# Sheet1.net
KiCad netlist of a schematic drawn in Altium Designer
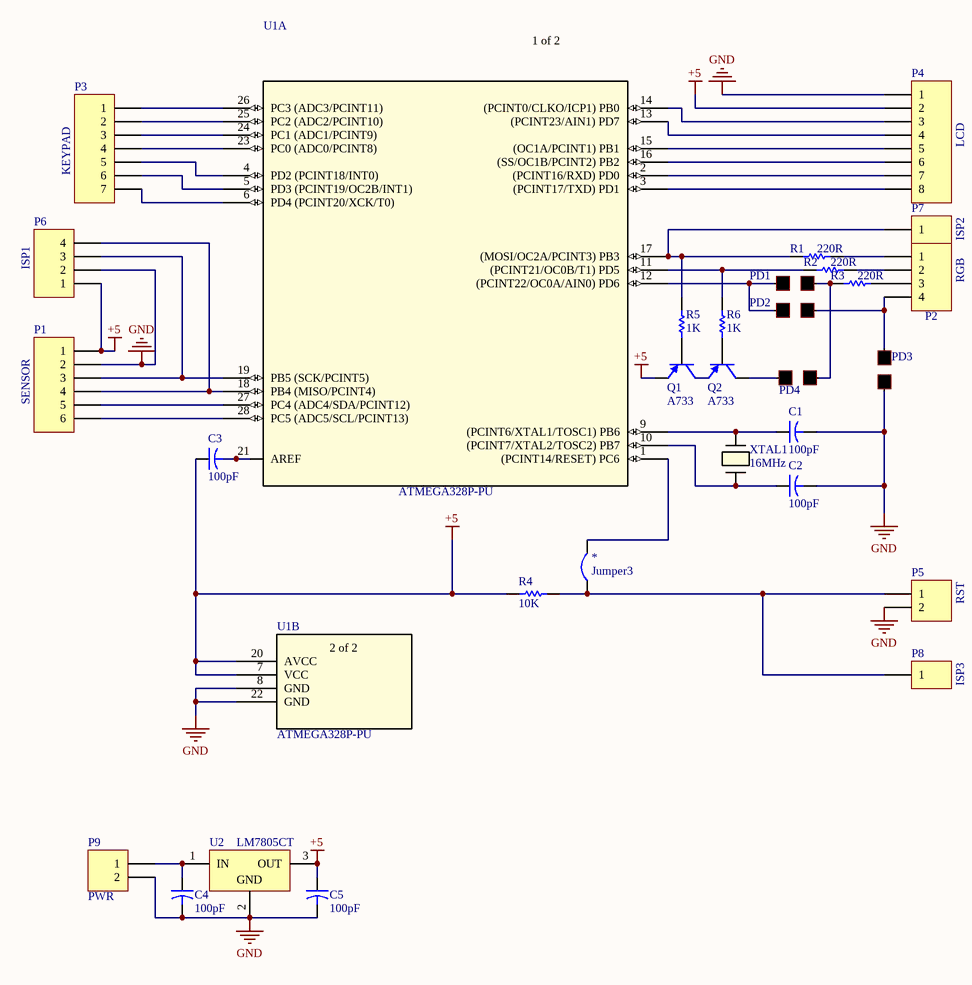
[diagram p0: Sheet1.SchDoc]

(export (version "E")
  (design (tool "Eeschema 10.0.6"))
  (components
    (comp (ref "*") (value "Jumper3") (footprint "JUMPER3") (libsource (lib "Common Parts") (part "Jumper3")))
    (comp (ref "C1")
      (value "100pF")
      (footprint "CAP1")
      (description "Capacitor")
      (fields (field (name "PUBLISHER") "Altium Limited"))
      (libsource (lib "Common Parts") (part "Cap1"))
    )
    (comp (ref "C2")
      (value "100pF")
      (footprint "CAP1")
      (description "Capacitor")
      (fields (field (name "PUBLISHER") "Altium Limited"))
      (libsource (lib "Common Parts") (part "Cap1"))
    )
    (comp (ref "C3")
      (value "100pF")
      (footprint "CAP1")
      (description "Capacitor")
      (fields (field (name "PUBLISHER") "Altium Limited"))
      (libsource (lib "Common Parts") (part "Cap1"))
    )
    (comp (ref "C4")
      (value "100pF")
      (footprint "CAP1")
      (description "Capacitor")
      (fields (field (name "PUBLISHER") "Altium Limited"))
      (libsource (lib "Common Parts") (part "Cap1"))
    )
    (comp (ref "C5")
      (value "100pF")
      (footprint "CAP1")
      (description "Capacitor")
      (fields (field (name "PUBLISHER") "Altium Limited"))
      (libsource (lib "Common Parts") (part "Cap1"))
    )
    (comp (ref "P1")
      (value "SENSOR")
      (footprint "H6")
      (description "Header, 6-Pin")
      (fields (field (name "PUBLISHER") "Altium Limited"))
      (libsource (lib "Miscellaneous Connectors") (part "Header 6"))
    )
    (comp (ref "P2")
      (value "RGB")
      (footprint "H4")
      (description "Header, 4-Pin")
      (fields (field (name "PUBLISHER") "Altium Limited"))
      (libsource (lib "") (part "Header 4_1"))
    )
    (comp (ref "P3")
      (value "KEYPAD")
      (footprint "H7")
      (description "Header, 7-Pin")
      (fields (field (name "PUBLISHER") "Altium Limited"))
      (libsource (lib "Miscellaneous Connectors") (part "Header 7"))
    )
    (comp (ref "P4")
      (value "LCD")
      (footprint "H8")
      (description "Header, 8-Pin")
      (fields (field (name "PUBLISHER") "Altium Limited"))
      (libsource (lib "Miscellaneous Connectors") (part "Header 8"))
    )
    (comp (ref "P5")
      (value "RST")
      (footprint "H2")
      (description "Header, 2-Pin")
      (fields (field (name "PUBLISHER") "Altium Limited"))
      (libsource (lib "Miscellaneous Connectors") (part "Header 2"))
    )
    (comp (ref "P6")
      (value "ISP1")
      (footprint "H4")
      (description "Header, 4-Pin")
      (fields (field (name "PUBLISHER") "Altium Limited"))
      (libsource (lib "Miscellaneous Connectors") (part "Header 4"))
    )
    (comp (ref "P7")
      (value "ISP2")
      (footprint "H1")
      (description "Header, 1-Pin")
      (fields (field (name "PUBLISHER") "Altium Limited"))
      (libsource (lib "Footprints_lib") (part "Header 1"))
    )
    (comp (ref "P8")
      (value "ISP3")
      (footprint "H1")
      (description "Header, 1-Pin")
      (fields (field (name "PUBLISHER") "Altium Limited"))
      (libsource (lib "Footprints_lib") (part "Header 1"))
    )
    (comp (ref "P9")
      (value "PWR")
      (footprint "H2_PWR")
      (description "Header, 2-Pin")
      (fields (field (name "PUBLISHER") "Altium Limited"))
      (libsource (lib "Footprints_lib") (part "Header 2"))
    )
    (comp (ref "PD1")
      (value "Pad2")
      (footprint "PAD2")
      (description "Square Pad")
      (libsource (lib "") (part "Pad2_1"))
    )
    (comp (ref "PD2")
      (value "Pad2")
      (footprint "PAD2")
      (description "Square Pad")
      (libsource (lib "") (part "Pad2_1"))
    )
    (comp (ref "PD3")
      (value "Pad2")
      (footprint "PAD2")
      (description "Square Pad")
      (libsource (lib "Common Parts") (part "Pad2"))
    )
    (comp (ref "PD4")
      (value "Pad2")
      (footprint "PAD2")
      (description "Square Pad")
      (libsource (lib "") (part "Pad2_2"))
    )
    (comp (ref "Q1")
      (value "A733")
      (footprint "TO-92_ONS")
      (description "PNP General Purpose Transistor")
      (fields (field (name "PUBLISHER") "Altium Limited"))
      (libsource (lib "Common Parts") (part "A733"))
    )
    (comp (ref "Q2")
      (value "A733")
      (footprint "TO-92_ONS")
      (description "PNP General Purpose Transistor")
      (fields (field (name "PUBLISHER") "Altium Limited"))
      (libsource (lib "Common Parts") (part "A733"))
    )
    (comp (ref "R1")
      (value "220R")
      (footprint "RES")
      (description "Resistor")
      (fields (field (name "PUBLISHER") "Altium Limited"))
      (libsource (lib "Miscellaneous Devices") (part "Res1"))
    )
    (comp (ref "R2")
      (value "220R")
      (footprint "RES")
      (description "Resistor")
      (fields (field (name "PUBLISHER") "Altium Limited"))
      (libsource (lib "Miscellaneous Devices") (part "Res1"))
    )
    (comp (ref "R3")
      (value "220R")
      (footprint "RES")
      (description "Resistor")
      (fields (field (name "PUBLISHER") "Altium Limited"))
      (libsource (lib "Miscellaneous Devices") (part "Res1"))
    )
    (comp (ref "R4")
      (value "10K")
      (footprint "RES")
      (description "Resistor")
      (fields (field (name "PUBLISHER") "Altium Limited"))
      (libsource (lib "Common Parts") (part "Res1"))
    )
    (comp (ref "R5")
      (value "1K")
      (footprint "RES")
      (description "Resistor")
      (fields (field (name "PUBLISHER") "Altium Limited"))
      (libsource (lib "Miscellaneous Devices") (part "Res1"))
    )
    (comp (ref "R6")
      (value "1K")
      (footprint "RES")
      (description "Resistor")
      (fields (field (name "PUBLISHER") "Altium Limited"))
      (libsource (lib "Miscellaneous Devices") (part "Res1"))
    )
    (comp (ref "U1")
      (value "ATMEGA328P-PU")
      (footprint "28P3_ATM")
      (description "No Description Available")
      (fields (field (name "COPYRIGHT") "Copyright (C) 2018 Accelerated Designs. All rights reserved"))
      (libsource (lib "") (part "ATMEGA328P-PU_1"))
    )
    (comp (ref "U2")
      (value "LM7805CT")
      (footprint "FAIR-TO-220-3")
      (description "Positive Voltage Regulator, 5 V, 1 A, -40 to 125 degC, 3-Pin TO-220, RoHS, Tube")
      (fields (field (name "MANUFACTURER") "FairchildSemiconductor"))
      (libsource (lib "Altium Content Vault") (part "FAIR-LM7805CT-TO220-3"))
    )
    (comp (ref "XTAL1")
      (value "16MHz")
      (footprint "XTAL_9B_TXC")
      (description "No Description Available")
      (fields
        (field (name "MANUFACTURER_PART_NUMBER") "9B-11.0592MAAJ-B")
        (field (name "COPYRIGHT") "Copyright (C) 2018 Accelerated Designs. All rights reserved")
      )
      (libsource (lib "XTAL") (part "9B-11.0592MAAJ-B"))
    )
  )
  (nets
    (net (code "1") (name "+5") (class "Default")
      (node (ref "C3") (pin "1") (pinfunction "1_1") (pintype "passive"))
      (node (ref "C5") (pin "1") (pinfunction "1_1") (pintype "passive"))
      (node (ref "P1") (pin "1") (pinfunction "1_1") (pintype "passive"))
      (node (ref "P4") (pin "2") (pinfunction "2_2") (pintype "passive"))
      (node (ref "P6") (pin "1") (pinfunction "1_1") (pintype "passive"))
      (node (ref "Q1") (pin "1") (pinfunction "E_1") (pintype "passive"))
      (node (ref "R4") (pin "2") (pinfunction "2_2") (pintype "passive"))
      (node (ref "U1") (pin "20") (pinfunction "AVCC_20") (pintype "power_in"))
      (node (ref "U1") (pin "7") (pinfunction "VCC_7") (pintype "power_in"))
      (node (ref "U2") (pin "3") (pinfunction "OUT_3") (pintype "power_in"))
    )
    (net (code "2") (name "GND") (class "Default")
      (node (ref "C1") (pin "2") (pinfunction "2_2") (pintype "passive"))
      (node (ref "C2") (pin "2") (pinfunction "2_2") (pintype "passive"))
      (node (ref "C4") (pin "2") (pinfunction "2_2") (pintype "passive"))
      (node (ref "C5") (pin "2") (pinfunction "2_2") (pintype "passive"))
      (node (ref "P1") (pin "2") (pinfunction "2_2") (pintype "passive"))
      (node (ref "P4") (pin "1") (pinfunction "1_1") (pintype "passive"))
      (node (ref "P5") (pin "2") (pinfunction "2_2") (pintype "passive"))
      (node (ref "P6") (pin "2") (pinfunction "2_2") (pintype "passive"))
      (node (ref "P9") (pin "2") (pinfunction "2_2") (pintype "passive"))
      (node (ref "PD3") (pin "1") (pinfunction "1_1") (pintype "passive"))
      (node (ref "U1") (pin "22") (pinfunction "GND_22") (pintype "power_in"))
      (node (ref "U1") (pin "8") (pinfunction "GND_8") (pintype "power_in"))
      (node (ref "U2") (pin "2") (pinfunction "GND_2") (pintype "power_in"))
    )
    (net (code "3") (name "Net-(*-Pad1)") (class "Default")
      (node (ref "*") (pin "1") (pinfunction "1_1") (pintype "passive"))
      (node (ref "P5") (pin "1") (pinfunction "1_1") (pintype "passive"))
      (node (ref "P8") (pin "1") (pinfunction "1_1") (pintype "passive"))
      (node (ref "R4") (pin "1") (pinfunction "1_1") (pintype "passive"))
    )
    (net (code "4") (name "Net-(P2-Pad1)") (class "Default")
      (node (ref "P2") (pin "1") (pinfunction "1_1") (pintype "passive"))
      (node (ref "R1") (pin "2") (pinfunction "2_2") (pintype "passive"))
    )
    (net (code "5") (name "Net-(P2-Pad2)") (class "Default")
      (node (ref "P2") (pin "2") (pinfunction "2_2") (pintype "passive"))
      (node (ref "R2") (pin "2") (pinfunction "2_2") (pintype "passive"))
    )
    (net (code "6") (name "Net-(P2-Pad3)") (class "Default")
      (node (ref "P2") (pin "3") (pinfunction "3_3") (pintype "passive"))
      (node (ref "R3") (pin "2") (pinfunction "2_2") (pintype "passive"))
    )
    (net (code "7") (name "Net-(P2-Pad4)") (class "Default")
      (node (ref "P2") (pin "4") (pinfunction "4_4") (pintype "passive"))
      (node (ref "PD2") (pin "2") (pinfunction "2_2") (pintype "passive"))
      (node (ref "PD3") (pin "2") (pinfunction "2_2") (pintype "passive"))
    )
    (net (code "8") (name "Net-(PD1-Pad2)") (class "Default")
      (node (ref "PD1") (pin "2") (pinfunction "2_2") (pintype "passive"))
      (node (ref "PD4") (pin "1") (pinfunction "1_1") (pintype "passive"))
      (node (ref "R3") (pin "1") (pinfunction "1_1") (pintype "passive"))
    )
    (net (code "9") (name "Net-(Q1-B)") (class "Default")
      (node (ref "Q1") (pin "3") (pinfunction "B_3") (pintype "passive"))
      (node (ref "R5") (pin "1") (pinfunction "1_1") (pintype "passive"))
    )
    (net (code "10") (name "Net-(Q1-C)") (class "Default")
      (node (ref "Q1") (pin "2") (pinfunction "C_2") (pintype "passive"))
      (node (ref "Q2") (pin "1") (pinfunction "E_1") (pintype "passive"))
    )
    (net (code "11") (name "Net-(Q2-B)") (class "Default")
      (node (ref "Q2") (pin "3") (pinfunction "B_3") (pintype "passive"))
      (node (ref "R6") (pin "1") (pinfunction "1_1") (pintype "passive"))
    )
    (net (code "12") (name "Net-(Q2-C)") (class "Default")
      (node (ref "PD4") (pin "2") (pinfunction "2_2") (pintype "passive"))
      (node (ref "Q2") (pin "2") (pinfunction "C_2") (pintype "passive"))
    )
    (net (code "13") (name "Net-(U1A-(MOSI{slash}OC2A{slash}PCINT3)_PB3)") (class "Default")
      (node (ref "P7") (pin "1") (pinfunction "1_1") (pintype "passive"))
      (node (ref "R1") (pin "1") (pinfunction "1_1") (pintype "passive"))
      (node (ref "R5") (pin "2") (pinfunction "2_2") (pintype "passive"))
      (node (ref "U1") (pin "17") (pinfunction "(MOSI/OC2A/PCINT3)_PB3_17") (pintype "bidirectional"))
    )
    (net (code "14") (name "Net-(U1A-(OC1A{slash}PCINT1)_PB1)") (class "Default")
      (node (ref "P4") (pin "5") (pinfunction "5_5") (pintype "passive"))
      (node (ref "U1") (pin "15") (pinfunction "(OC1A/PCINT1)_PB1_15") (pintype "bidirectional"))
    )
    (net (code "15") (name "Net-(U1A-(PCINT0{slash}CLKO{slash}ICP1)_PB0)") (class "Default")
      (node (ref "P4") (pin "3") (pinfunction "3_3") (pintype "passive"))
      (node (ref "U1") (pin "14") (pinfunction "(PCINT0/CLKO/ICP1)_PB0_14") (pintype "bidirectional"))
    )
    (net (code "16") (name "Net-(U1A-(PCINT6{slash}XTAL1{slash}TOSC1)_PB6)") (class "Default")
      (node (ref "C1") (pin "1") (pinfunction "1_1") (pintype "passive"))
      (node (ref "U1") (pin "9") (pinfunction "(PCINT6/XTAL1/TOSC1)_PB6_9") (pintype "bidirectional"))
      (node (ref "XTAL1") (pin "2") (pinfunction "2_2") (pintype "passive"))
    )
    (net (code "17") (name "Net-(U1A-(PCINT7{slash}XTAL2{slash}TOSC2)_PB7)") (class "Default")
      (node (ref "C2") (pin "1") (pinfunction "1_1") (pintype "passive"))
      (node (ref "U1") (pin "10") (pinfunction "(PCINT7/XTAL2/TOSC2)_PB7_10") (pintype "bidirectional"))
      (node (ref "XTAL1") (pin "1") (pinfunction "1_1") (pintype "passive"))
    )
    (net (code "18") (name "Net-(U1A-(PCINT14{slash}RESET)_PC6)") (class "Default")
      (node (ref "*") (pin "2") (pinfunction "2_2") (pintype "passive"))
      (node (ref "U1") (pin "1") (pinfunction "(PCINT14/RESET)_PC6_1") (pintype "bidirectional"))
    )
    (net (code "19") (name "Net-(U1A-(PCINT16{slash}RXD)_PD0)") (class "Default")
      (node (ref "P4") (pin "7") (pinfunction "7_7") (pintype "passive"))
      (node (ref "U1") (pin "2") (pinfunction "(PCINT16/RXD)_PD0_2") (pintype "bidirectional"))
    )
    (net (code "20") (name "Net-(U1A-(PCINT17{slash}TXD)_PD1)") (class "Default")
      (node (ref "P4") (pin "8") (pinfunction "8_8") (pintype "passive"))
      (node (ref "U1") (pin "3") (pinfunction "(PCINT17/TXD)_PD1_3") (pintype "bidirectional"))
    )
    (net (code "21") (name "Net-(U1A-(PCINT21{slash}OC0B{slash}T1)_PD5)") (class "Default")
      (node (ref "R2") (pin "1") (pinfunction "1_1") (pintype "passive"))
      (node (ref "R6") (pin "2") (pinfunction "2_2") (pintype "passive"))
      (node (ref "U1") (pin "11") (pinfunction "(PCINT21/OC0B/T1)_PD5_11") (pintype "bidirectional"))
    )
    (net (code "22") (name "Net-(U1A-(PCINT22{slash}OC0A{slash}AIN0)_PD6)") (class "Default")
      (node (ref "PD1") (pin "1") (pinfunction "1_1") (pintype "passive"))
      (node (ref "PD2") (pin "1") (pinfunction "1_1") (pintype "passive"))
      (node (ref "U1") (pin "12") (pinfunction "(PCINT22/OC0A/AIN0)_PD6_12") (pintype "bidirectional"))
    )
    (net (code "23") (name "Net-(U1A-(PCINT23{slash}AIN1)_PD7)") (class "Default")
      (node (ref "P4") (pin "4") (pinfunction "4_4") (pintype "passive"))
      (node (ref "U1") (pin "13") (pinfunction "(PCINT23/AIN1)_PD7_13") (pintype "bidirectional"))
    )
    (net (code "24") (name "Net-(U1A-(SS{slash}OC1B{slash}PCINT2)_PB2)") (class "Default")
      (node (ref "P4") (pin "6") (pinfunction "6_6") (pintype "passive"))
      (node (ref "U1") (pin "16") (pinfunction "(SS/OC1B/PCINT2)_PB2_16") (pintype "bidirectional"))
    )
    (net (code "25") (name "Net-(U1A-AREF)") (class "Default")
      (node (ref "C3") (pin "2") (pinfunction "2_2") (pintype "passive"))
      (node (ref "U1") (pin "21") (pinfunction "AREF_21") (pintype "passive"))
    )
    (net (code "26") (name "Net-(U1A-PB4_(MISO{slash}PCINT4))") (class "Default")
      (node (ref "P1") (pin "4") (pinfunction "4_4") (pintype "passive"))
      (node (ref "P6") (pin "4") (pinfunction "4_4") (pintype "passive"))
      (node (ref "U1") (pin "18") (pinfunction "PB4_(MISO/PCINT4)_18") (pintype "bidirectional"))
    )
    (net (code "27") (name "Net-(U1A-PB5_(SCK{slash}PCINT5))") (class "Default")
      (node (ref "P1") (pin "3") (pinfunction "3_3") (pintype "passive"))
      (node (ref "P6") (pin "3") (pinfunction "3_3") (pintype "passive"))
      (node (ref "U1") (pin "19") (pinfunction "PB5_(SCK/PCINT5)_19") (pintype "bidirectional"))
    )
    (net (code "28") (name "Net-(U1A-PC0_(ADC0{slash}PCINT8))") (class "Default")
      (node (ref "P3") (pin "4") (pinfunction "4_4") (pintype "passive"))
      (node (ref "U1") (pin "23") (pinfunction "PC0_(ADC0/PCINT8)_23") (pintype "bidirectional"))
    )
    (net (code "29") (name "Net-(U1A-PC1_(ADC1{slash}PCINT9))") (class "Default")
      (node (ref "P3") (pin "3") (pinfunction "3_3") (pintype "passive"))
      (node (ref "U1") (pin "24") (pinfunction "PC1_(ADC1/PCINT9)_24") (pintype "bidirectional"))
    )
    (net (code "30") (name "Net-(U1A-PC2_(ADC2{slash}PCINT10))") (class "Default")
      (node (ref "P3") (pin "2") (pinfunction "2_2") (pintype "passive"))
      (node (ref "U1") (pin "25") (pinfunction "PC2_(ADC2/PCINT10)_25") (pintype "bidirectional"))
    )
    (net (code "31") (name "Net-(U1A-PC3_(ADC3{slash}PCINT11))") (class "Default")
      (node (ref "P3") (pin "1") (pinfunction "1_1") (pintype "passive"))
      (node (ref "U1") (pin "26") (pinfunction "PC3_(ADC3/PCINT11)_26") (pintype "bidirectional"))
    )
    (net (code "32") (name "Net-(U1A-PC4_(ADC4{slash}SDA{slash}PCINT12))") (class "Default")
      (node (ref "P1") (pin "5") (pinfunction "5_5") (pintype "passive"))
      (node (ref "U1") (pin "27") (pinfunction "PC4_(ADC4/SDA/PCINT12)_27") (pintype "bidirectional"))
    )
    (net (code "33") (name "Net-(U1A-PC5_(ADC5{slash}SCL{slash}PCINT13))") (class "Default")
      (node (ref "P1") (pin "6") (pinfunction "6_6") (pintype "passive"))
      (node (ref "U1") (pin "28") (pinfunction "PC5_(ADC5/SCL/PCINT13)_28") (pintype "bidirectional"))
    )
    (net (code "34") (name "Net-(U1A-PD2_(PCINT18{slash}INT0))") (class "Default")
      (node (ref "P3") (pin "5") (pinfunction "5_5") (pintype "passive"))
      (node (ref "U1") (pin "4") (pinfunction "PD2_(PCINT18/INT0)_4") (pintype "bidirectional"))
    )
    (net (code "35") (name "Net-(U1A-PD3_(PCINT19{slash}OC2B{slash}INT1))") (class "Default")
      (node (ref "P3") (pin "6") (pinfunction "6_6") (pintype "passive"))
      (node (ref "U1") (pin "5") (pinfunction "PD3_(PCINT19/OC2B/INT1)_5") (pintype "bidirectional"))
    )
    (net (code "36") (name "Net-(U1A-PD4_(PCINT20{slash}XCK{slash}T0))") (class "Default")
      (node (ref "P3") (pin "7") (pinfunction "7_7") (pintype "passive"))
      (node (ref "U1") (pin "6") (pinfunction "PD4_(PCINT20/XCK/T0)_6") (pintype "bidirectional"))
    )
    (net (code "37") (name "Net-(U2-IN)") (class "Default")
      (node (ref "C4") (pin "1") (pinfunction "1_1") (pintype "passive"))
      (node (ref "P9") (pin "1") (pinfunction "1_1") (pintype "passive"))
      (node (ref "U2") (pin "1") (pinfunction "IN_1") (pintype "power_in"))
    )
  )
)
